# RFM95_LoRa_Shield_v0_2.net
KiCad netlist of a schematic drawn in EAGLE
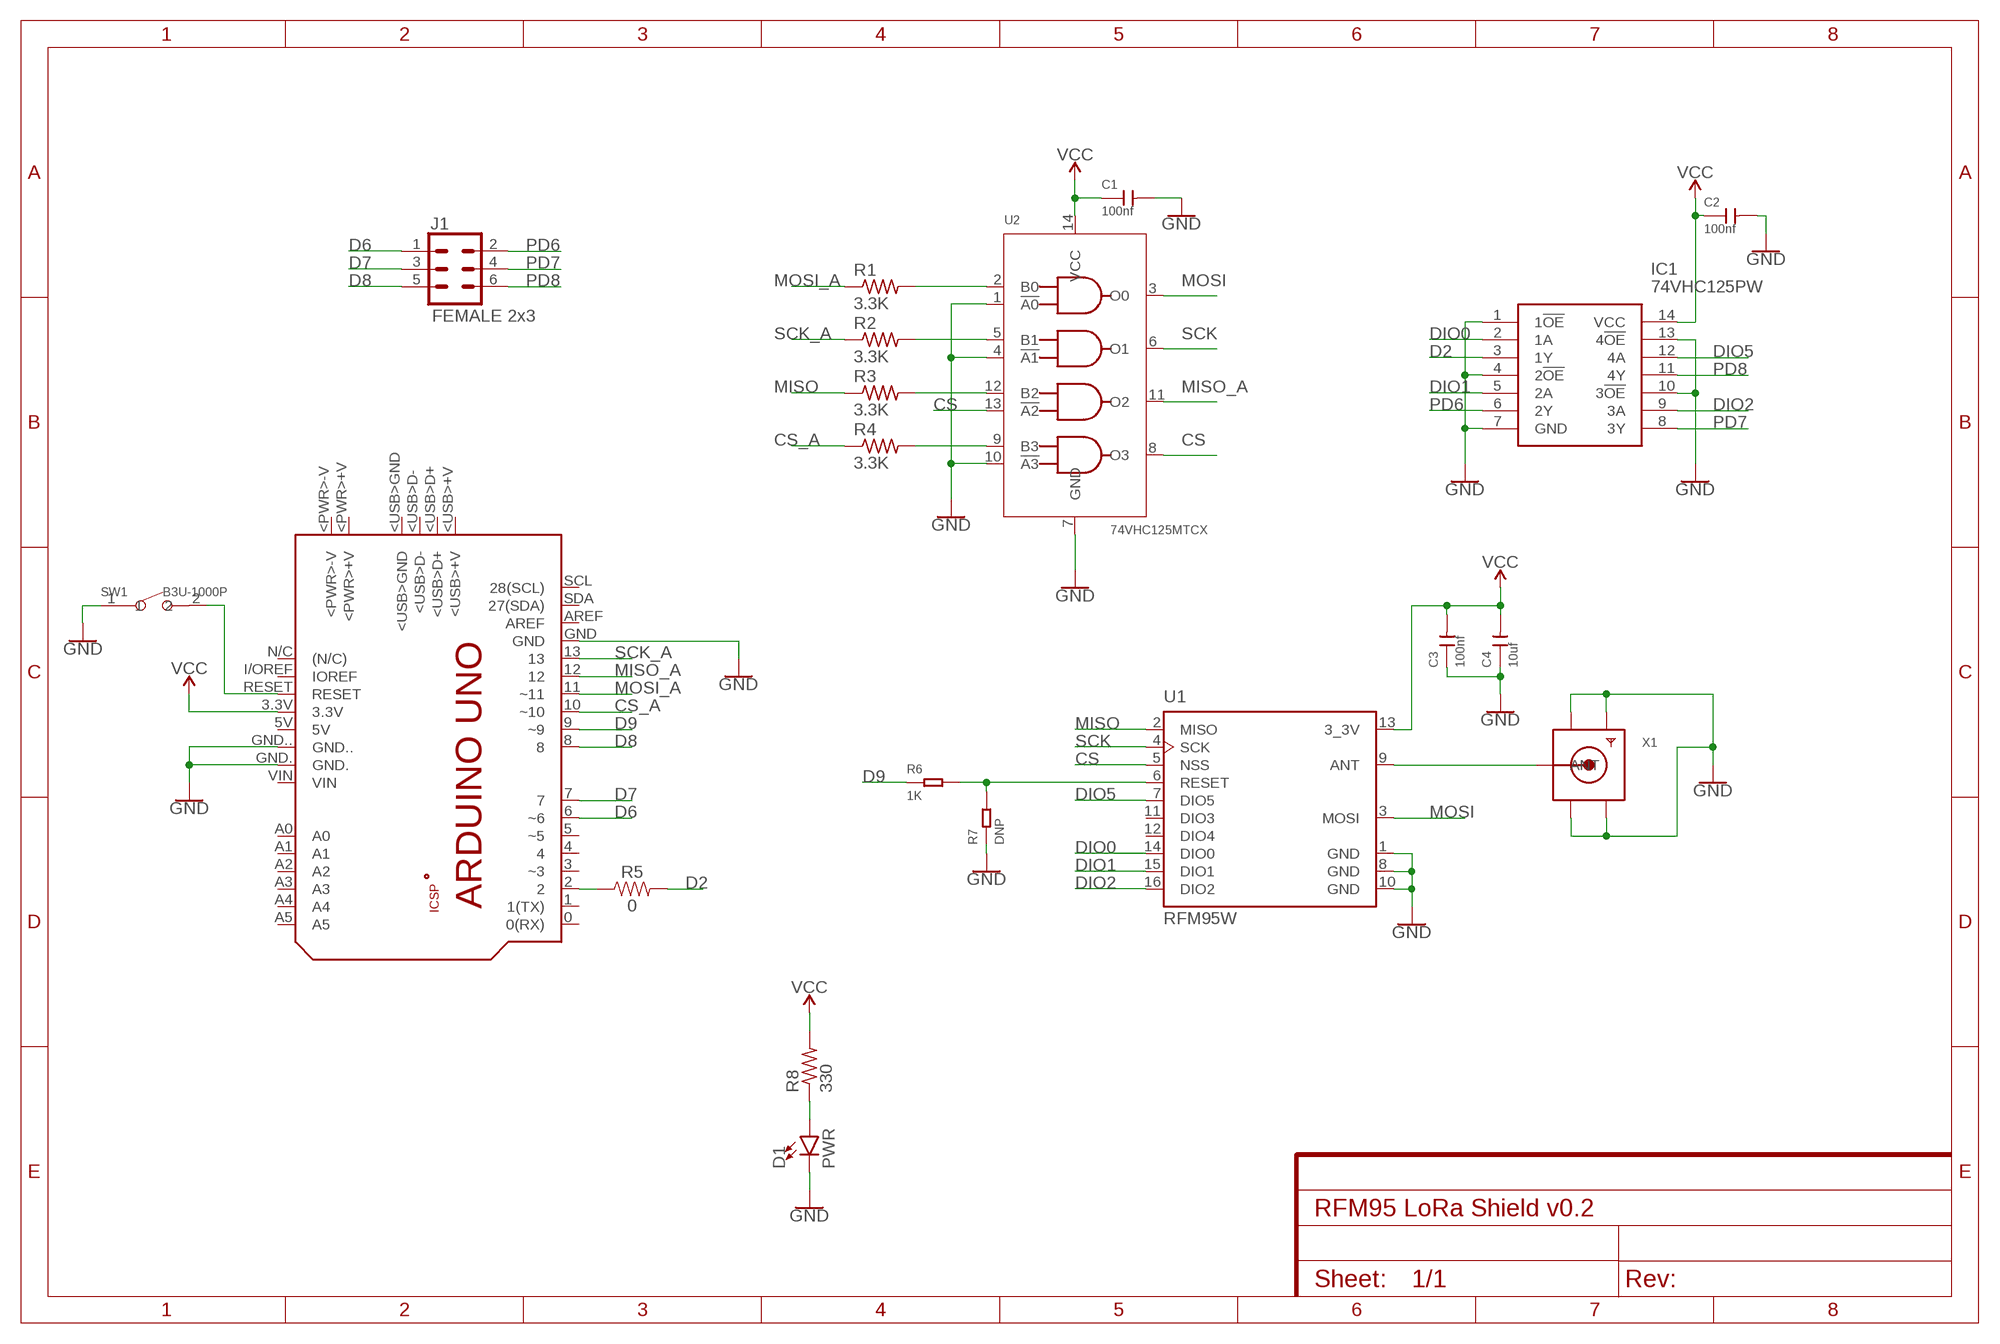
[diagram p0: schematic, sheet 1]

(export (version "E")
  (design (tool "Eeschema 10.0.6"))
  (components
    (comp (ref "C1")
      (value "100nf")
      (footprint "eagle-import:C0805")
      (fields (field (name "MPN") "CC0805KRX7R9BB104"))
      (libsource (lib "eagle-import") (part "CERAMIC-100NF-50V-10%-X7R(0805)"))
    )
    (comp (ref "C2")
      (value "100nf")
      (footprint "eagle-import:C0805")
      (fields (field (name "MPN") "CC0805KRX7R9BB104"))
      (libsource (lib "eagle-import") (part "CERAMIC-100NF-50V-10%-X7R(0805)"))
    )
    (comp (ref "C3")
      (value "100nf")
      (footprint "eagle-import:C0805")
      (fields (field (name "MPN") "CC0805KRX7R9BB104"))
      (libsource (lib "eagle-import") (part "CERAMIC-100NF-50V-10%-X7R(0805)"))
    )
    (comp (ref "C4")
      (value "10uf")
      (footprint "eagle-import:C0805")
      (fields (field (name "MPN") "CC0805KKX5R8BB106"))
      (libsource (lib "eagle-import") (part "CERAMIC-10UF-25V-10%-X5R(0805)"))
    )
    (comp (ref "D1")
      (value "PWR")
      (footprint "eagle-import:LED-1206")
      (libsource (lib "eagle-import") (part "LED-GREEN1206"))
    )
    (comp (ref "IC1")
      (value "74VHC125PW")
      (footprint "eagle-import:SOP65P640X110-14N")
      (fields (field (name "MANUFACTURER_PART_NUMBER") "74VHC125PW,118"))
      (libsource (lib "eagle-import") (part "74VHC125PW,118"))
    )
    (comp (ref "J1")
      (value "FEMALE 2x3")
      (footprint "eagle-import:2X3")
      (libsource (lib "eagle-import") (part "CONN_03X2FEMALE"))
    )
    (comp (ref "PCB1")
      (value "Arduino Uno")
      (footprint "eagle-import:ARDUINO_UNO")
      (libsource (lib "eagle-import") (part "ARDUINO_UNO"))
    )
    (comp (ref "R1")
      (value "3.3K")
      (footprint "eagle-import:M0805")
      (libsource (lib "eagle-import") (part "R-US_M0805"))
    )
    (comp (ref "R2")
      (value "3.3K")
      (footprint "eagle-import:M0805")
      (libsource (lib "eagle-import") (part "R-US_M0805"))
    )
    (comp (ref "R3")
      (value "3.3K")
      (footprint "eagle-import:M0805")
      (libsource (lib "eagle-import") (part "R-US_M0805"))
    )
    (comp (ref "R4")
      (value "3.3K")
      (footprint "eagle-import:M0805")
      (libsource (lib "eagle-import") (part "R-US_M0805"))
    )
    (comp (ref "R5")
      (value "0")
      (footprint "eagle-import:0603")
      (libsource (lib "eagle-import") (part "0OHM-0603-1/10W-5%"))
    )
    (comp (ref "R6")
      (value "1K")
      (footprint "eagle-import:R0805")
      (fields (field (name "MPN") "RC0805JR-071KL"))
      (libsource (lib "eagle-import") (part "SMD-RES-1K-5%-1/8W(0805)"))
    )
    (comp (ref "R7")
      (value "DNP")
      (footprint "eagle-import:R0805")
      (fields (field (name "MPN") "RC0805JR-071KL"))
      (libsource (lib "eagle-import") (part "SMD-RES-1K-5%-1/8W(0805)"))
    )
    (comp (ref "R8")
      (value "330")
      (footprint "eagle-import:M0805")
      (libsource (lib "eagle-import") (part "R-US_M0805"))
    )
    (comp (ref "SW1")
      (value "B3U-1000P")
      (footprint "eagle-import:SW2-2.6-3.0X2.5X1.2+0.4MM")
      (fields (field (name "MPN") "B3U-1000P-2P-SMD"))
      (libsource (lib "eagle-import") (part "SMD-BUTTON(2P-3.0X2.5X1.2+0.4MM)-B3U-1000P-2P-SMD"))
    )
    (comp (ref "U1")
      (value "RFM95W")
      (footprint "eagle-import:XCVR_RFM95W-868S2")
      (fields (field (name "MF") "RF") (field (name "MP") "RFM95W-868S2"))
      (libsource (lib "eagle-import") (part "RFM95W-868S2"))
    )
    (comp (ref "U2")
      (value "74VHC125MTCX")
      (footprint "eagle-import:TSSOP14-0.65-5X4.4MM")
      (libsource (lib "eagle-import") (part "LOGIC-74VHC125MTCX(TSSOP14)"))
    )
    (comp (ref "X1")
      (value "SMACONNECTOR")
      (footprint "eagle-import:SMA90_DIP")
      (libsource (lib "eagle-import") (part "SMACONNECTOR"))
    )
  )
  (nets
    (net (code "1") (name "/CS") (class "Default")
      (node (ref "U1") (pin "5") (pinfunction "NSS_5") (pintype "input"))
      (node (ref "U2") (pin "13") (pinfunction "~{A2}_13") (pintype "input"))
      (node (ref "U2") (pin "8") (pinfunction "O3_8") (pintype "bidirectional"))
    )
    (net (code "2") (name "/CS_A") (class "Default")
      (node (ref "PCB1") (pin "10") (pinfunction "~{10}_10") (pintype "bidirectional"))
      (node (ref "R4") (pin "1") (pinfunction "1_1") (pintype "passive"))
    )
    (net (code "3") (name "/D2") (class "Default")
      (node (ref "IC1") (pin "3") (pinfunction "1Y_3") (pintype "bidirectional"))
      (node (ref "R5") (pin "2") (pinfunction "2_2") (pintype "passive"))
    )
    (net (code "4") (name "/D6") (class "Default")
      (node (ref "J1") (pin "1") (pinfunction "1_1") (pintype "bidirectional"))
      (node (ref "PCB1") (pin "6") (pinfunction "~{6}_6") (pintype "bidirectional"))
    )
    (net (code "5") (name "/D7") (class "Default")
      (node (ref "J1") (pin "3") (pinfunction "3_3") (pintype "bidirectional"))
      (node (ref "PCB1") (pin "7") (pinfunction "7_7") (pintype "bidirectional"))
    )
    (net (code "6") (name "/D8") (class "Default")
      (node (ref "J1") (pin "5") (pinfunction "5_5") (pintype "bidirectional"))
      (node (ref "PCB1") (pin "8") (pinfunction "8_8") (pintype "bidirectional"))
    )
    (net (code "7") (name "/D9") (class "Default")
      (node (ref "PCB1") (pin "9") (pinfunction "~{9}_9") (pintype "bidirectional"))
      (node (ref "R6") (pin "1") (pinfunction "1_1") (pintype "passive"))
    )
    (net (code "8") (name "/DIO0") (class "Default")
      (node (ref "IC1") (pin "2") (pinfunction "1A_2") (pintype "bidirectional"))
      (node (ref "U1") (pin "14") (pinfunction "DIO0_14") (pintype "bidirectional"))
    )
    (net (code "9") (name "/DIO1") (class "Default")
      (node (ref "IC1") (pin "5") (pinfunction "2A_5") (pintype "bidirectional"))
      (node (ref "U1") (pin "15") (pinfunction "DIO1_15") (pintype "bidirectional"))
    )
    (net (code "10") (name "/DIO2") (class "Default")
      (node (ref "IC1") (pin "9") (pinfunction "3A_9") (pintype "bidirectional"))
      (node (ref "U1") (pin "16") (pinfunction "DIO2_16") (pintype "bidirectional"))
    )
    (net (code "11") (name "/DIO5") (class "Default")
      (node (ref "IC1") (pin "12") (pinfunction "4A_12") (pintype "bidirectional"))
      (node (ref "U1") (pin "7") (pinfunction "DIO5_7") (pintype "bidirectional"))
    )
    (net (code "12") (name "/MISO") (class "Default")
      (node (ref "R3") (pin "1") (pinfunction "1_1") (pintype "passive"))
      (node (ref "U1") (pin "2") (pinfunction "MISO_2") (pintype "input"))
    )
    (net (code "13") (name "/MISO_A") (class "Default")
      (node (ref "PCB1") (pin "12") (pinfunction "12_12") (pintype "bidirectional"))
      (node (ref "U2") (pin "11") (pinfunction "O2_11") (pintype "bidirectional"))
    )
    (net (code "14") (name "/MOSI") (class "Default")
      (node (ref "U1") (pin "3") (pinfunction "MOSI_3") (pintype "output"))
      (node (ref "U2") (pin "3") (pinfunction "O0_3") (pintype "bidirectional"))
    )
    (net (code "15") (name "/MOSI_A") (class "Default")
      (node (ref "PCB1") (pin "11") (pinfunction "~{11}_11") (pintype "bidirectional"))
      (node (ref "R1") (pin "1") (pinfunction "1_1") (pintype "passive"))
    )
    (net (code "16") (name "/PD6") (class "Default")
      (node (ref "IC1") (pin "6") (pinfunction "2Y_6") (pintype "bidirectional"))
      (node (ref "J1") (pin "2") (pinfunction "2_2") (pintype "bidirectional"))
    )
    (net (code "17") (name "/PD7") (class "Default")
      (node (ref "IC1") (pin "8") (pinfunction "3Y_8") (pintype "bidirectional"))
      (node (ref "J1") (pin "4") (pinfunction "4_4") (pintype "bidirectional"))
    )
    (net (code "18") (name "/PD8") (class "Default")
      (node (ref "IC1") (pin "11") (pinfunction "4Y_11") (pintype "bidirectional"))
      (node (ref "J1") (pin "6") (pinfunction "6_6") (pintype "bidirectional"))
    )
    (net (code "19") (name "/SCK") (class "Default")
      (node (ref "U1") (pin "4") (pinfunction "SCK_4") (pintype "input"))
      (node (ref "U2") (pin "6") (pinfunction "O1_6") (pintype "bidirectional"))
    )
    (net (code "20") (name "/SCK_A") (class "Default")
      (node (ref "PCB1") (pin "13") (pinfunction "13_13") (pintype "bidirectional"))
      (node (ref "R2") (pin "1") (pinfunction "1_1") (pintype "passive"))
    )
    (net (code "21") (name "GND") (class "Default")
      (node (ref "C1") (pin "2") (pinfunction "2_2") (pintype "passive"))
      (node (ref "C2") (pin "2") (pinfunction "2_2") (pintype "passive"))
      (node (ref "C3") (pin "1") (pinfunction "1_1") (pintype "passive"))
      (node (ref "C4") (pin "1") (pinfunction "1_1") (pintype "passive"))
      (node (ref "D1") (pin "C") (pinfunction "C_C") (pintype "passive"))
      (node (ref "IC1") (pin "1") (pinfunction "1~{OE}_1") (pintype "bidirectional"))
      (node (ref "IC1") (pin "10") (pinfunction "3~{OE}_10") (pintype "bidirectional"))
      (node (ref "IC1") (pin "13") (pinfunction "4~{OE}_13") (pintype "bidirectional"))
      (node (ref "IC1") (pin "4") (pinfunction "2~{OE}_4") (pintype "bidirectional"))
      (node (ref "IC1") (pin "7") (pinfunction "GND_7") (pintype "bidirectional"))
      (node (ref "PCB1") (pin "GND") (pinfunction "GND_GND") (pintype "bidirectional"))
      (node (ref "PCB1") (pin "GND.") (pinfunction "GND._GND.") (pintype "bidirectional"))
      (node (ref "PCB1") (pin "GND..") (pinfunction "GND.._GND..") (pintype "bidirectional"))
      (node (ref "R7") (pin "1") (pinfunction "1_1") (pintype "passive"))
      (node (ref "SW1") (pin "1") (pinfunction "1_1") (pintype "bidirectional"))
      (node (ref "U1") (pin "1") (pinfunction "GND_1") (pintype "power_in"))
      (node (ref "U1") (pin "10") (pinfunction "GND_10") (pintype "power_in"))
      (node (ref "U1") (pin "8") (pinfunction "GND_8") (pintype "power_in"))
      (node (ref "U2") (pin "1") (pinfunction "~{A0}_1") (pintype "power_in"))
      (node (ref "U2") (pin "10") (pinfunction "~{A3}_10") (pintype "bidirectional"))
      (node (ref "U2") (pin "4") (pinfunction "~{A1}_4") (pintype "power_in"))
      (node (ref "U2") (pin "7") (pinfunction "GND_7") (pintype "power_in"))
      (node (ref "X1") (pin "GND1") (pinfunction "GND1_GND1") (pintype "power_in"))
      (node (ref "X1") (pin "GND2") (pinfunction "GND2_GND2") (pintype "power_in"))
      (node (ref "X1") (pin "GND3") (pinfunction "GND3_GND3") (pintype "power_in"))
      (node (ref "X1") (pin "GND4") (pinfunction "GND4_GND4") (pintype "power_in"))
    )
    (net (code "22") (name "Net-(D1-PadA)") (class "Default")
      (node (ref "D1") (pin "A") (pinfunction "A_A") (pintype "passive"))
      (node (ref "R8") (pin "1") (pinfunction "1_1") (pintype "passive"))
    )
    (net (code "23") (name "Net-(PCB1-Pad2)") (class "Default")
      (node (ref "PCB1") (pin "2") (pinfunction "2_2") (pintype "bidirectional"))
      (node (ref "R5") (pin "1") (pinfunction "1_1") (pintype "passive"))
    )
    (net (code "24") (name "Net-(PCB1-PadRESET)") (class "Default")
      (node (ref "PCB1") (pin "RESET") (pinfunction "RESET_RESET") (pintype "bidirectional"))
      (node (ref "SW1") (pin "2") (pinfunction "2_2") (pintype "bidirectional"))
    )
    (net (code "25") (name "Net-(U1-ANT)") (class "Default")
      (node (ref "U1") (pin "9") (pinfunction "ANT_9") (pintype "passive"))
      (node (ref "X1") (pin "ANTENNA") (pinfunction "ANT_ANTENNA") (pintype "bidirectional"))
    )
    (net (code "26") (name "Net-(U1-RESET)") (class "Default")
      (node (ref "R6") (pin "2") (pinfunction "2_2") (pintype "passive"))
      (node (ref "R7") (pin "2") (pinfunction "2_2") (pintype "passive"))
      (node (ref "U1") (pin "6") (pinfunction "RESET_6") (pintype "bidirectional"))
    )
    (net (code "27") (name "Net-(U2-B0)") (class "Default")
      (node (ref "R1") (pin "2") (pinfunction "2_2") (pintype "passive"))
      (node (ref "U2") (pin "2") (pinfunction "B0_2") (pintype "bidirectional"))
    )
    (net (code "28") (name "Net-(U2-B1)") (class "Default")
      (node (ref "R2") (pin "2") (pinfunction "2_2") (pintype "passive"))
      (node (ref "U2") (pin "5") (pinfunction "B1_5") (pintype "bidirectional"))
    )
    (net (code "29") (name "Net-(U2-B2)") (class "Default")
      (node (ref "R3") (pin "2") (pinfunction "2_2") (pintype "passive"))
      (node (ref "U2") (pin "12") (pinfunction "B2_12") (pintype "bidirectional"))
    )
    (net (code "30") (name "Net-(U2-B3)") (class "Default")
      (node (ref "R4") (pin "2") (pinfunction "2_2") (pintype "passive"))
      (node (ref "U2") (pin "9") (pinfunction "B3_9") (pintype "bidirectional"))
    )
    (net (code "31") (name "VCC") (class "Default")
      (node (ref "C1") (pin "1") (pinfunction "1_1") (pintype "passive"))
      (node (ref "C2") (pin "1") (pinfunction "1_1") (pintype "passive"))
      (node (ref "C3") (pin "2") (pinfunction "2_2") (pintype "passive"))
      (node (ref "C4") (pin "2") (pinfunction "2_2") (pintype "passive"))
      (node (ref "IC1") (pin "14") (pinfunction "VCC_14") (pintype "bidirectional"))
      (node (ref "PCB1") (pin "3.3V") (pinfunction "3.3V_3.3V") (pintype "bidirectional"))
      (node (ref "R8") (pin "2") (pinfunction "2_2") (pintype "passive"))
      (node (ref "U1") (pin "13") (pinfunction "3_3V_13") (pintype "power_in"))
      (node (ref "U2") (pin "14") (pinfunction "VCC_14") (pintype "power_in"))
    )
    (net (code "32") (name "unconnected-(PCB1-(N{slash}C)-PadN{slash}C)") (class "Default")
      (node (ref "PCB1") (pin "N/C") (pinfunction "(N/C)_N/C") (pintype "bidirectional"))
    )
    (net (code "33") (name "unconnected-(PCB1-0(RX)-Pad0)") (class "Default")
      (node (ref "PCB1") (pin "0") (pinfunction "0(RX)_0") (pintype "bidirectional"))
    )
    (net (code "34") (name "unconnected-(PCB1-1(TX)-Pad1)") (class "Default")
      (node (ref "PCB1") (pin "1") (pinfunction "1(TX)_1") (pintype "bidirectional"))
    )
    (net (code "35") (name "unconnected-(PCB1-27(SDA)-PadSDA)") (class "Default")
      (node (ref "PCB1") (pin "SDA") (pinfunction "27(SDA)_SDA") (pintype "bidirectional"))
    )
    (net (code "36") (name "unconnected-(PCB1-28(SCL)-PadSCL)") (class "Default")
      (node (ref "PCB1") (pin "SCL") (pinfunction "28(SCL)_SCL") (pintype "bidirectional"))
    )
    (net (code "37") (name "unconnected-(PCB1-IOREF-PadI{slash}OREF)") (class "Default")
      (node (ref "PCB1") (pin "I/OREF") (pinfunction "IOREF_I/OREF") (pintype "bidirectional"))
    )
    (net (code "38") (name "unconnected-(PCB1-Pad+5V)") (class "Default")
      (node (ref "PCB1") (pin "+5V") (pinfunction "+5V_+5V") (pintype "bidirectional"))
    )
    (net (code "39") (name "unconnected-(PCB1-Pad4)") (class "Default")
      (node (ref "PCB1") (pin "4") (pinfunction "4_4") (pintype "bidirectional"))
    )
    (net (code "40") (name "unconnected-(PCB1-Pad5V)") (class "Default")
      (node (ref "PCB1") (pin "5V") (pinfunction "5V_5V") (pintype "bidirectional"))
    )
    (net (code "41") (name "unconnected-(PCB1-Pad<PWR>+V)") (class "Default")
      (node (ref "PCB1") (pin "<PWR>+V") (pinfunction "<PWR>+V_<PWR>+V") (pintype "bidirectional"))
    )
    (net (code "42") (name "unconnected-(PCB1-Pad<PWR>-V)") (class "Default")
      (node (ref "PCB1") (pin "<PWR>-V") (pinfunction "<PWR>-V_<PWR>-V") (pintype "bidirectional"))
    )
    (net (code "43") (name "unconnected-(PCB1-Pad<USB>+V)") (class "Default")
      (node (ref "PCB1") (pin "<USB>+V") (pinfunction "<USB>+V_<USB>+V") (pintype "bidirectional"))
    )
    (net (code "44") (name "unconnected-(PCB1-Pad<USB>D+)") (class "Default")
      (node (ref "PCB1") (pin "<USB>D+") (pinfunction "<USB>D+_<USB>D+") (pintype "bidirectional"))
    )
    (net (code "45") (name "unconnected-(PCB1-Pad<USB>D-)") (class "Default")
      (node (ref "PCB1") (pin "<USB>D-") (pinfunction "<USB>D-_<USB>D-") (pintype "bidirectional"))
    )
    (net (code "46") (name "unconnected-(PCB1-Pad<USB>GND)") (class "Default")
      (node (ref "PCB1") (pin "<USB>GND") (pinfunction "<USB>GND_<USB>GND") (pintype "bidirectional"))
    )
    (net (code "47") (name "unconnected-(PCB1-PadA0)") (class "Default")
      (node (ref "PCB1") (pin "A0") (pinfunction "A0_A0") (pintype "bidirectional"))
    )
    (net (code "48") (name "unconnected-(PCB1-PadA1)") (class "Default")
      (node (ref "PCB1") (pin "A1") (pinfunction "A1_A1") (pintype "bidirectional"))
    )
    (net (code "49") (name "unconnected-(PCB1-PadA2)") (class "Default")
      (node (ref "PCB1") (pin "A2") (pinfunction "A2_A2") (pintype "bidirectional"))
    )
    (net (code "50") (name "unconnected-(PCB1-PadA3)") (class "Default")
      (node (ref "PCB1") (pin "A3") (pinfunction "A3_A3") (pintype "bidirectional"))
    )
    (net (code "51") (name "unconnected-(PCB1-PadA4)") (class "Default")
      (node (ref "PCB1") (pin "A4") (pinfunction "A4_A4") (pintype "bidirectional"))
    )
    (net (code "52") (name "unconnected-(PCB1-PadA5)") (class "Default")
      (node (ref "PCB1") (pin "A5") (pinfunction "A5_A5") (pintype "bidirectional"))
    )
    (net (code "53") (name "unconnected-(PCB1-PadAREF)") (class "Default")
      (node (ref "PCB1") (pin "AREF") (pinfunction "AREF_AREF") (pintype "bidirectional"))
    )
    (net (code "54") (name "unconnected-(PCB1-PadGND_)") (class "Default")
      (node (ref "PCB1") (pin "GND_") (pinfunction "GND__GND_") (pintype "bidirectional"))
    )
    (net (code "55") (name "unconnected-(PCB1-PadMISO)") (class "Default")
      (node (ref "PCB1") (pin "MISO") (pinfunction "MISO_MISO") (pintype "bidirectional"))
    )
    (net (code "56") (name "unconnected-(PCB1-PadMOSI)") (class "Default")
      (node (ref "PCB1") (pin "MOSI") (pinfunction "MOSI_MOSI") (pintype "bidirectional"))
    )
    (net (code "57") (name "unconnected-(PCB1-PadRESET.)") (class "Default")
      (node (ref "PCB1") (pin "RESET.") (pinfunction "RESET._RESET.") (pintype "bidirectional"))
    )
    (net (code "58") (name "unconnected-(PCB1-PadSCK)") (class "Default")
      (node (ref "PCB1") (pin "SCK") (pinfunction "SCK_SCK") (pintype "bidirectional"))
    )
    (net (code "59") (name "unconnected-(PCB1-PadVIN)") (class "Default")
      (node (ref "PCB1") (pin "VIN") (pinfunction "VIN_VIN") (pintype "bidirectional"))
    )
    (net (code "60") (name "unconnected-(PCB1-~{3}-Pad3)") (class "Default")
      (node (ref "PCB1") (pin "3") (pinfunction "~{3}_3") (pintype "bidirectional"))
    )
    (net (code "61") (name "unconnected-(PCB1-~{5}-Pad5)") (class "Default")
      (node (ref "PCB1") (pin "5") (pinfunction "~{5}_5") (pintype "bidirectional"))
    )
    (net (code "62") (name "unconnected-(U1-DIO3-Pad11)") (class "Default")
      (node (ref "U1") (pin "11") (pinfunction "DIO3_11") (pintype "bidirectional"))
    )
    (net (code "63") (name "unconnected-(U1-DIO4-Pad12)") (class "Default")
      (node (ref "U1") (pin "12") (pinfunction "DIO4_12") (pintype "bidirectional"))
    )
  )
)
